# messverstaerker-opamp-proto.net
KiCad netlist of a schematic drawn in EAGLE
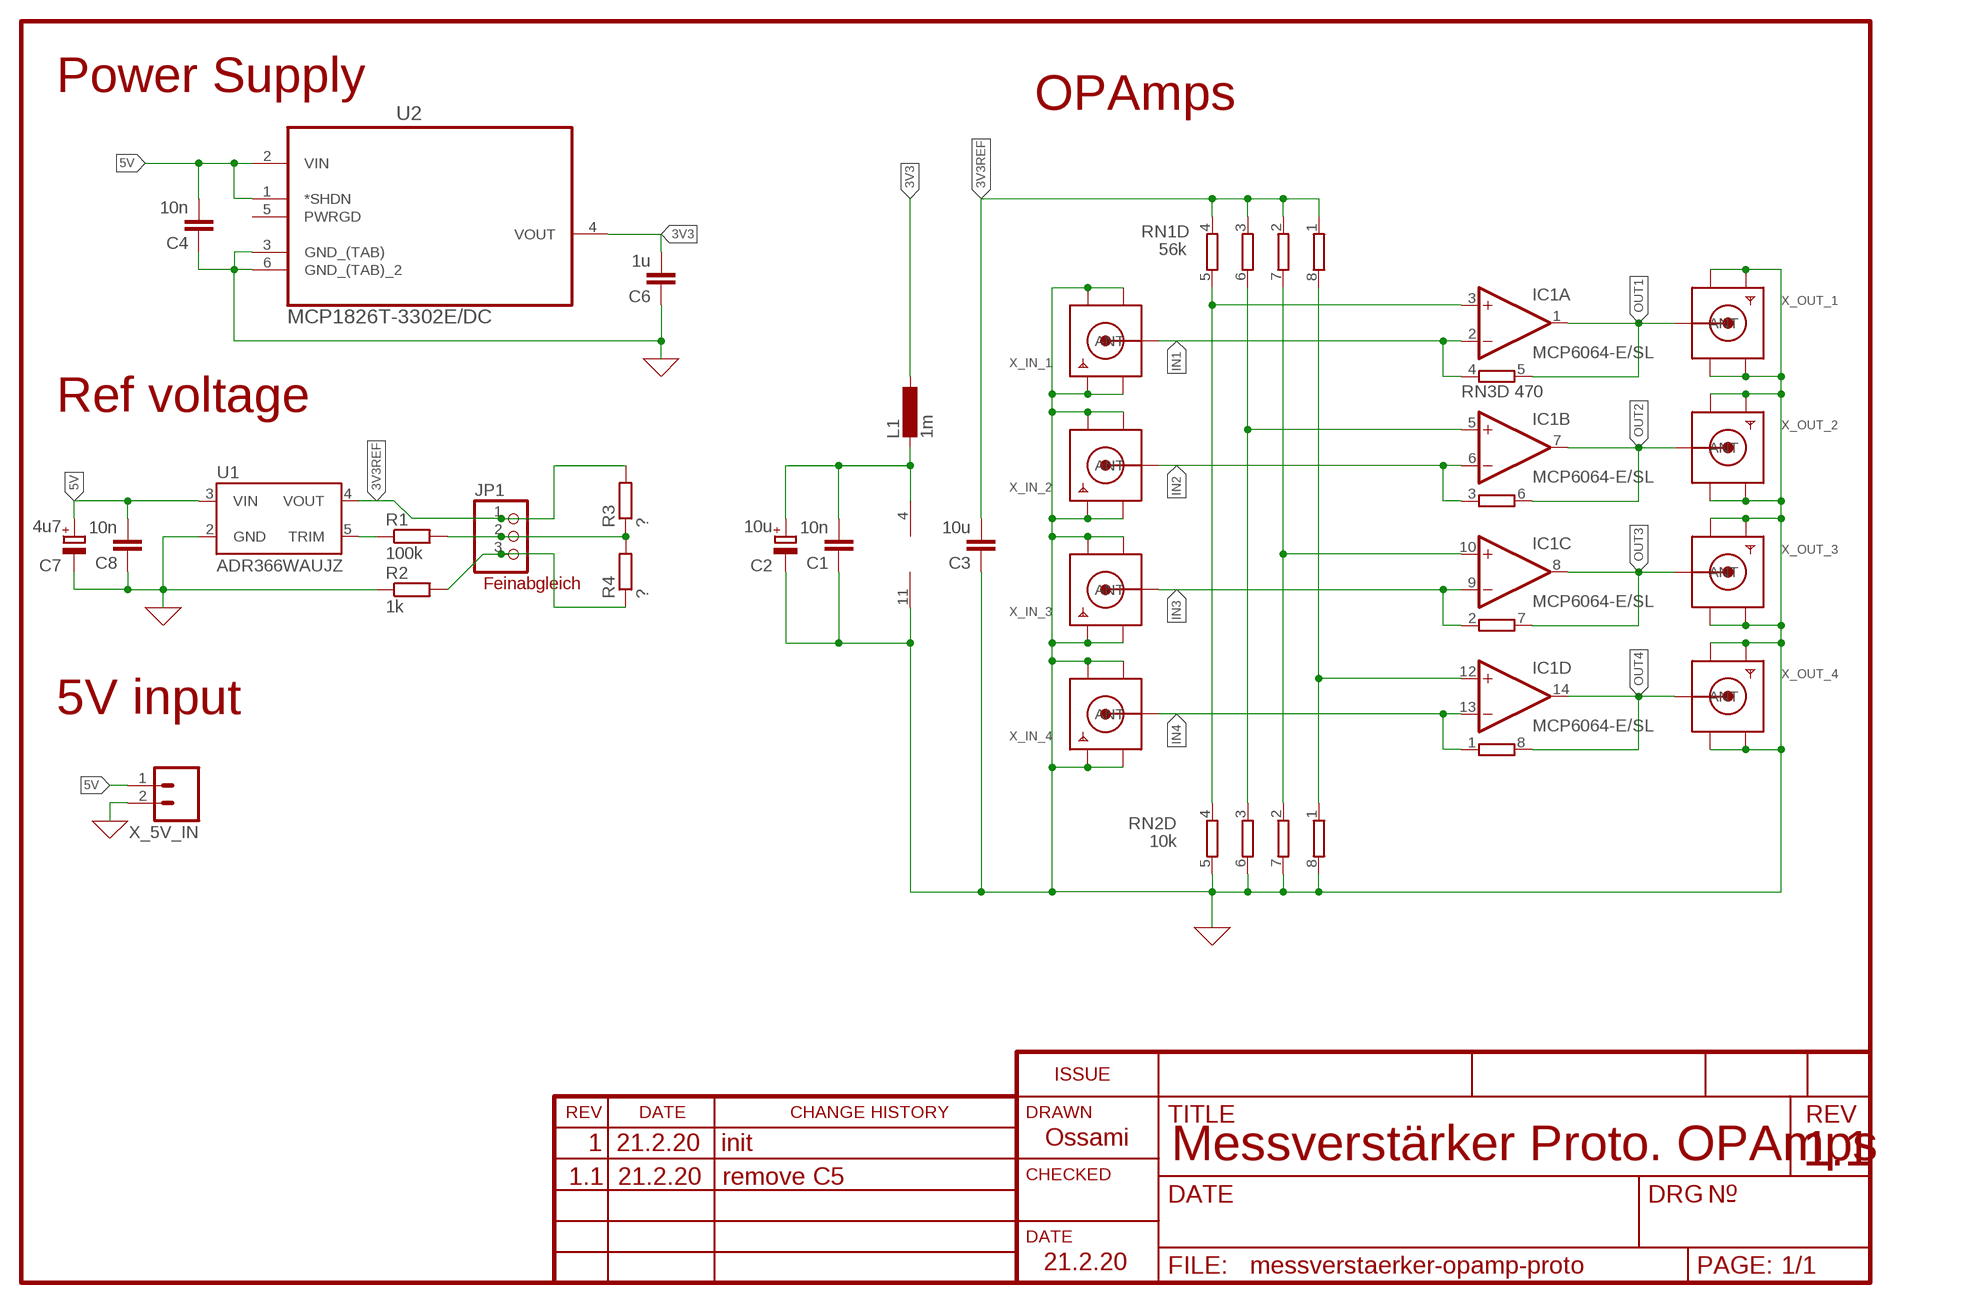
[diagram p0: schematic, sheet 1]

(export (version "E")
  (design (tool "Eeschema 10.0.6"))
  (components
    (comp (ref "C1")
      (value "10n")
      (footprint "eagle-import:C0805")
      (libsource (lib "eagle-import") (part "C-EUC0805"))
    )
    (comp (ref "C2")
      (value "10u")
      (footprint "eagle-import:153CLV-0810")
      (libsource (lib "eagle-import") (part "CPOL-EU153CLV-0810"))
    )
    (comp (ref "C3")
      (value "10u")
      (footprint "eagle-import:C0805")
      (libsource (lib "eagle-import") (part "C-EUC0805"))
    )
    (comp (ref "C4")
      (value "10n")
      (footprint "eagle-import:C0805")
      (libsource (lib "eagle-import") (part "C-EUC0805"))
    )
    (comp (ref "C6")
      (value "1u")
      (footprint "eagle-import:C0805")
      (libsource (lib "eagle-import") (part "C-EUC0805"))
    )
    (comp (ref "C7")
      (value "4u7")
      (footprint "eagle-import:153CLV-0810")
      (libsource (lib "eagle-import") (part "CPOL-EU153CLV-0810"))
    )
    (comp (ref "C8")
      (value "10n")
      (footprint "eagle-import:C0805")
      (libsource (lib "eagle-import") (part "C-EUC0805"))
    )
    (comp (ref "IC1")
      (value "MCP6064-E/SL")
      (footprint "eagle-import:SO14")
      (libsource (lib "eagle-import") (part "MCP604SL"))
    )
    (comp (ref "JP1")
      (value "PINHD-1X3")
      (footprint "eagle-import:1X03")
      (libsource (lib "eagle-import") (part "PINHD-1X3"))
    )
    (comp (ref "L1")
      (value "1m")
      (footprint "eagle-import:L5650M")
      (libsource (lib "eagle-import") (part "L-EUL5650M"))
    )
    (comp (ref "R1")
      (value "100k")
      (footprint "eagle-import:R0805")
      (libsource (lib "eagle-import") (part "R-EU_R0805"))
    )
    (comp (ref "R2")
      (value "1k")
      (footprint "eagle-import:R0805")
      (libsource (lib "eagle-import") (part "R-EU_R0805"))
    )
    (comp (ref "R3")
      (value "?")
      (footprint "eagle-import:R0805")
      (libsource (lib "eagle-import") (part "R-EU_R0805"))
    )
    (comp (ref "R4")
      (value "?")
      (footprint "eagle-import:R0805")
      (libsource (lib "eagle-import") (part "R-EU_R0805"))
    )
    (comp (ref "RN1")
      (value "56k")
      (footprint "eagle-import:EXBS8V")
      (libsource (lib "eagle-import") (part "4R-NEXBS8V"))
    )
    (comp (ref "RN2")
      (value "10k")
      (footprint "eagle-import:EXBS8V")
      (libsource (lib "eagle-import") (part "4R-NEXBS8V"))
    )
    (comp (ref "RN3")
      (value "470")
      (footprint "eagle-import:EXBS8V")
      (libsource (lib "eagle-import") (part "4R-NEXBS8V"))
    )
    (comp (ref "U1")
      (value "ADR366WAUJZ")
      (footprint "eagle-import:SOT23-5")
      (libsource (lib "eagle-import") (part "ADR36UJZ_"))
    )
    (comp (ref "U2")
      (value "MCP1826T-3302E/DC")
      (footprint "eagle-import:SOT230P700X180-6N")
      (fields (field (name "MF") "Microchip") (field (name "MP") "MCP1826T-3002E/DC"))
      (libsource (lib "eagle-import") (part "MCP1826T-3002E/DC"))
    )
    (comp (ref "X_5V_IN")
      (value "M02LOCK")
      (footprint "eagle-import:1X02_LOCK")
      (libsource (lib "eagle-import") (part "M02LOCK"))
    )
    (comp (ref "X_IN_1")
      (value "SMACONNECTOR_EDGE")
      (footprint "eagle-import:SMA_EDGELAUNCH")
      (libsource (lib "eagle-import") (part "SMACONNECTOR_EDGE"))
    )
    (comp (ref "X_IN_2")
      (value "SMACONNECTOR_EDGE")
      (footprint "eagle-import:SMA_EDGELAUNCH")
      (libsource (lib "eagle-import") (part "SMACONNECTOR_EDGE"))
    )
    (comp (ref "X_IN_3")
      (value "SMACONNECTOR_EDGE")
      (footprint "eagle-import:SMA_EDGELAUNCH")
      (libsource (lib "eagle-import") (part "SMACONNECTOR_EDGE"))
    )
    (comp (ref "X_IN_4")
      (value "SMACONNECTOR_EDGE")
      (footprint "eagle-import:SMA_EDGELAUNCH")
      (libsource (lib "eagle-import") (part "SMACONNECTOR_EDGE"))
    )
    (comp (ref "X_OUT_1")
      (value "SMACONNECTOR_EDGE")
      (footprint "eagle-import:SMA_EDGELAUNCH")
      (libsource (lib "eagle-import") (part "SMACONNECTOR_EDGE"))
    )
    (comp (ref "X_OUT_2")
      (value "SMACONNECTOR_EDGE")
      (footprint "eagle-import:SMA_EDGELAUNCH")
      (libsource (lib "eagle-import") (part "SMACONNECTOR_EDGE"))
    )
    (comp (ref "X_OUT_3")
      (value "SMACONNECTOR_EDGE")
      (footprint "eagle-import:SMA_EDGELAUNCH")
      (libsource (lib "eagle-import") (part "SMACONNECTOR_EDGE"))
    )
    (comp (ref "X_OUT_4")
      (value "SMACONNECTOR_EDGE")
      (footprint "eagle-import:SMA_EDGELAUNCH")
      (libsource (lib "eagle-import") (part "SMACONNECTOR_EDGE"))
    )
  )
  (nets
    (net (code "1") (name "3V3") (class "Default")
      (node (ref "C6") (pin "2") (pinfunction "2_2") (pintype "passive"))
      (node (ref "L1") (pin "1") (pinfunction "1_1") (pintype "passive"))
      (node (ref "U2") (pin "4") (pinfunction "VOUT_4") (pintype "output"))
    )
    (net (code "2") (name "3V3REF") (class "Default")
      (node (ref "C3") (pin "2") (pinfunction "2_2") (pintype "passive"))
      (node (ref "JP1") (pin "1") (pinfunction "1_1") (pintype "passive"))
      (node (ref "R3") (pin "2") (pinfunction "2_2") (pintype "passive"))
      (node (ref "RN1") (pin "1") (pinfunction "1_1") (pintype "passive"))
      (node (ref "RN1") (pin "2") (pinfunction "1_2") (pintype "passive"))
      (node (ref "RN1") (pin "3") (pinfunction "1_3") (pintype "passive"))
      (node (ref "RN1") (pin "4") (pinfunction "1_4") (pintype "passive"))
      (node (ref "U1") (pin "4") (pinfunction "VOUT_4") (pintype "power_in"))
    )
    (net (code "3") (name "5V") (class "Default")
      (node (ref "C4") (pin "2") (pinfunction "2_2") (pintype "passive"))
      (node (ref "C7") (pin "+") (pinfunction "+_+") (pintype "passive"))
      (node (ref "C8") (pin "2") (pinfunction "2_2") (pintype "passive"))
      (node (ref "U1") (pin "3") (pinfunction "VIN_3") (pintype "power_in"))
      (node (ref "U2") (pin "1") (pinfunction "*SHDN_1") (pintype "input"))
      (node (ref "U2") (pin "2") (pinfunction "VIN_2") (pintype "input"))
      (node (ref "X_5V_IN") (pin "1") (pinfunction "1_1") (pintype "passive"))
    )
    (net (code "4") (name "GND") (class "Default")
      (node (ref "C1") (pin "1") (pinfunction "1_1") (pintype "passive"))
      (node (ref "C2") (pin "-") (pinfunction "-_-") (pintype "passive"))
      (node (ref "C3") (pin "1") (pinfunction "1_1") (pintype "passive"))
      (node (ref "C4") (pin "1") (pinfunction "1_1") (pintype "passive"))
      (node (ref "C6") (pin "1") (pinfunction "1_1") (pintype "passive"))
      (node (ref "C7") (pin "-") (pinfunction "-_-") (pintype "passive"))
      (node (ref "C8") (pin "1") (pinfunction "1_1") (pintype "passive"))
      (node (ref "IC1") (pin "11") (pinfunction "V-_11") (pintype "power_in"))
      (node (ref "R2") (pin "1") (pinfunction "1_1") (pintype "passive"))
      (node (ref "RN2") (pin "5") (pinfunction "2_5") (pintype "passive"))
      (node (ref "RN2") (pin "6") (pinfunction "2_6") (pintype "passive"))
      (node (ref "RN2") (pin "7") (pinfunction "2_7") (pintype "passive"))
      (node (ref "RN2") (pin "8") (pinfunction "2_8") (pintype "passive"))
      (node (ref "U1") (pin "2") (pinfunction "GND_2") (pintype "power_in"))
      (node (ref "U2") (pin "3") (pinfunction "GND_(TAB)_3") (pintype "passive"))
      (node (ref "U2") (pin "6") (pinfunction "GND_(TAB)_2_6") (pintype "passive"))
      (node (ref "X_5V_IN") (pin "2") (pinfunction "2_2") (pintype "passive"))
      (node (ref "X_IN_1") (pin "GND@1") (pinfunction "GND4_GND@1") (pintype "power_in"))
      (node (ref "X_IN_1") (pin "GND@2") (pinfunction "GND3_GND@2") (pintype "power_in"))
      (node (ref "X_IN_1") (pin "GND@3") (pinfunction "GND2_GND@3") (pintype "power_in"))
      (node (ref "X_IN_1") (pin "GND@4") (pinfunction "GND1_GND@4") (pintype "power_in"))
      (node (ref "X_IN_2") (pin "GND@1") (pinfunction "GND4_GND@1") (pintype "power_in"))
      (node (ref "X_IN_2") (pin "GND@2") (pinfunction "GND3_GND@2") (pintype "power_in"))
      (node (ref "X_IN_2") (pin "GND@3") (pinfunction "GND2_GND@3") (pintype "power_in"))
      (node (ref "X_IN_2") (pin "GND@4") (pinfunction "GND1_GND@4") (pintype "power_in"))
      (node (ref "X_IN_3") (pin "GND@1") (pinfunction "GND4_GND@1") (pintype "power_in"))
      (node (ref "X_IN_3") (pin "GND@2") (pinfunction "GND3_GND@2") (pintype "power_in"))
      (node (ref "X_IN_3") (pin "GND@3") (pinfunction "GND2_GND@3") (pintype "power_in"))
      (node (ref "X_IN_3") (pin "GND@4") (pinfunction "GND1_GND@4") (pintype "power_in"))
      (node (ref "X_IN_4") (pin "GND@1") (pinfunction "GND4_GND@1") (pintype "power_in"))
      (node (ref "X_IN_4") (pin "GND@2") (pinfunction "GND3_GND@2") (pintype "power_in"))
      (node (ref "X_IN_4") (pin "GND@3") (pinfunction "GND2_GND@3") (pintype "power_in"))
      (node (ref "X_IN_4") (pin "GND@4") (pinfunction "GND1_GND@4") (pintype "power_in"))
      (node (ref "X_OUT_1") (pin "GND@1") (pinfunction "GND4_GND@1") (pintype "power_in"))
      (node (ref "X_OUT_1") (pin "GND@2") (pinfunction "GND3_GND@2") (pintype "power_in"))
      (node (ref "X_OUT_1") (pin "GND@3") (pinfunction "GND2_GND@3") (pintype "power_in"))
      (node (ref "X_OUT_1") (pin "GND@4") (pinfunction "GND1_GND@4") (pintype "power_in"))
      (node (ref "X_OUT_2") (pin "GND@1") (pinfunction "GND4_GND@1") (pintype "power_in"))
      (node (ref "X_OUT_2") (pin "GND@2") (pinfunction "GND3_GND@2") (pintype "power_in"))
      (node (ref "X_OUT_2") (pin "GND@3") (pinfunction "GND2_GND@3") (pintype "power_in"))
      (node (ref "X_OUT_2") (pin "GND@4") (pinfunction "GND1_GND@4") (pintype "power_in"))
      (node (ref "X_OUT_3") (pin "GND@1") (pinfunction "GND4_GND@1") (pintype "power_in"))
      (node (ref "X_OUT_3") (pin "GND@2") (pinfunction "GND3_GND@2") (pintype "power_in"))
      (node (ref "X_OUT_3") (pin "GND@3") (pinfunction "GND2_GND@3") (pintype "power_in"))
      (node (ref "X_OUT_3") (pin "GND@4") (pinfunction "GND1_GND@4") (pintype "power_in"))
      (node (ref "X_OUT_4") (pin "GND@1") (pinfunction "GND4_GND@1") (pintype "power_in"))
      (node (ref "X_OUT_4") (pin "GND@2") (pinfunction "GND3_GND@2") (pintype "power_in"))
      (node (ref "X_OUT_4") (pin "GND@3") (pinfunction "GND2_GND@3") (pintype "power_in"))
      (node (ref "X_OUT_4") (pin "GND@4") (pinfunction "GND1_GND@4") (pintype "power_in"))
    )
    (net (code "5") (name "IN1") (class "Default")
      (node (ref "IC1") (pin "2") (pinfunction "-IN_2") (pintype "input"))
      (node (ref "RN3") (pin "4") (pinfunction "1_4") (pintype "passive"))
      (node (ref "X_IN_1") (pin "P") (pinfunction "ANT_P") (pintype "bidirectional"))
    )
    (net (code "6") (name "IN2") (class "Default")
      (node (ref "IC1") (pin "6") (pinfunction "-IN_6") (pintype "input"))
      (node (ref "RN3") (pin "3") (pinfunction "1_3") (pintype "passive"))
      (node (ref "X_IN_2") (pin "P") (pinfunction "ANT_P") (pintype "bidirectional"))
    )
    (net (code "7") (name "IN3") (class "Default")
      (node (ref "IC1") (pin "9") (pinfunction "-IN_9") (pintype "input"))
      (node (ref "RN3") (pin "2") (pinfunction "1_2") (pintype "passive"))
      (node (ref "X_IN_3") (pin "P") (pinfunction "ANT_P") (pintype "bidirectional"))
    )
    (net (code "8") (name "IN4") (class "Default")
      (node (ref "IC1") (pin "13") (pinfunction "-IN_13") (pintype "input"))
      (node (ref "RN3") (pin "1") (pinfunction "1_1") (pintype "passive"))
      (node (ref "X_IN_4") (pin "P") (pinfunction "ANT_P") (pintype "bidirectional"))
    )
    (net (code "9") (name "Net-(IC1A-+IN)") (class "Default")
      (node (ref "IC1") (pin "3") (pinfunction "+IN_3") (pintype "input"))
      (node (ref "RN1") (pin "5") (pinfunction "2_5") (pintype "passive"))
      (node (ref "RN2") (pin "4") (pinfunction "1_4") (pintype "passive"))
    )
    (net (code "10") (name "Net-(IC1B-+IN)") (class "Default")
      (node (ref "IC1") (pin "5") (pinfunction "+IN_5") (pintype "input"))
      (node (ref "RN1") (pin "6") (pinfunction "2_6") (pintype "passive"))
      (node (ref "RN2") (pin "3") (pinfunction "1_3") (pintype "passive"))
    )
    (net (code "11") (name "Net-(IC1C-+IN)") (class "Default")
      (node (ref "IC1") (pin "10") (pinfunction "+IN_10") (pintype "input"))
      (node (ref "RN1") (pin "7") (pinfunction "2_7") (pintype "passive"))
      (node (ref "RN2") (pin "2") (pinfunction "1_2") (pintype "passive"))
    )
    (net (code "12") (name "Net-(IC1D-+IN)") (class "Default")
      (node (ref "IC1") (pin "12") (pinfunction "+IN_12") (pintype "input"))
      (node (ref "RN1") (pin "8") (pinfunction "2_8") (pintype "passive"))
      (node (ref "RN2") (pin "1") (pinfunction "1_1") (pintype "passive"))
    )
    (net (code "13") (name "Net-(IC1E-V+)") (class "Default")
      (node (ref "C1") (pin "2") (pinfunction "2_2") (pintype "passive"))
      (node (ref "C2") (pin "+") (pinfunction "+_+") (pintype "passive"))
      (node (ref "IC1") (pin "4") (pinfunction "V+_4") (pintype "power_in"))
      (node (ref "L1") (pin "2") (pinfunction "2_2") (pintype "passive"))
    )
    (net (code "14") (name "Net-(JP1-Pad2)") (class "Default")
      (node (ref "JP1") (pin "2") (pinfunction "2_2") (pintype "passive"))
      (node (ref "R1") (pin "2") (pinfunction "2_2") (pintype "passive"))
      (node (ref "R3") (pin "1") (pinfunction "1_1") (pintype "passive"))
      (node (ref "R4") (pin "2") (pinfunction "2_2") (pintype "passive"))
    )
    (net (code "15") (name "Net-(JP1-Pad3)") (class "Default")
      (node (ref "JP1") (pin "3") (pinfunction "3_3") (pintype "passive"))
      (node (ref "R2") (pin "2") (pinfunction "2_2") (pintype "passive"))
      (node (ref "R4") (pin "1") (pinfunction "1_1") (pintype "passive"))
    )
    (net (code "16") (name "Net-(U1-TRIM)") (class "Default")
      (node (ref "R1") (pin "1") (pinfunction "1_1") (pintype "passive"))
      (node (ref "U1") (pin "5") (pinfunction "TRIM_5") (pintype "passive"))
    )
    (net (code "17") (name "OUT1") (class "Default")
      (node (ref "IC1") (pin "1") (pinfunction "OUT_1") (pintype "output"))
      (node (ref "RN3") (pin "5") (pinfunction "2_5") (pintype "passive"))
      (node (ref "X_OUT_1") (pin "P") (pinfunction "ANT_P") (pintype "bidirectional"))
    )
    (net (code "18") (name "OUT2") (class "Default")
      (node (ref "IC1") (pin "7") (pinfunction "OUT_7") (pintype "output"))
      (node (ref "RN3") (pin "6") (pinfunction "2_6") (pintype "passive"))
      (node (ref "X_OUT_2") (pin "P") (pinfunction "ANT_P") (pintype "bidirectional"))
    )
    (net (code "19") (name "OUT3") (class "Default")
      (node (ref "IC1") (pin "8") (pinfunction "OUT_8") (pintype "output"))
      (node (ref "RN3") (pin "7") (pinfunction "2_7") (pintype "passive"))
      (node (ref "X_OUT_3") (pin "P") (pinfunction "ANT_P") (pintype "bidirectional"))
    )
    (net (code "20") (name "OUT4") (class "Default")
      (node (ref "IC1") (pin "14") (pinfunction "OUT_14") (pintype "output"))
      (node (ref "RN3") (pin "8") (pinfunction "2_8") (pintype "passive"))
      (node (ref "X_OUT_4") (pin "P") (pinfunction "ANT_P") (pintype "bidirectional"))
    )
    (net (code "21") (name "unconnected-(U2-PWRGD-Pad5)") (class "Default")
      (node (ref "U2") (pin "5") (pinfunction "PWRGD_5") (pintype "input"))
    )
  )
)
